# LM2596.net
KiCad netlist of a schematic drawn in Altium Designer
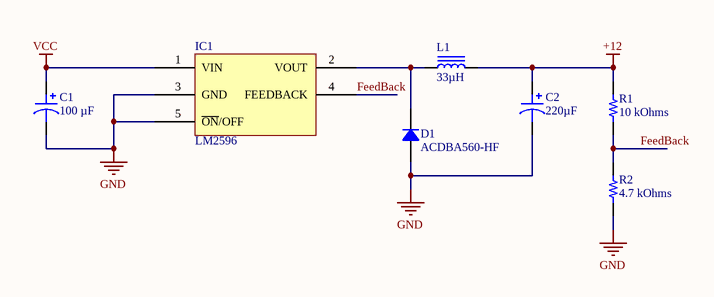
[diagram p0: LM2596.SchDoc]

(export (version "E")
  (design (tool "Eeschema 10.0.6"))
  (components
    (comp (ref "C1")
      (value "100 µF")
      (footprint "CAP AL TH D8 L3.5 H12.5")
      (description "CAP ALUM 100UF 20% 63V RADIAL")
      (fields
        (field (name "PART NUMBER") "ECA-1JM101")
        (field (name "MANUFACTURER") "Panasonic Electronic Components")
      )
      (libsource (lib "Celestial Altium Library - altium_library") (part "Polarised Capacitor"))
    )
    (comp (ref "C2")
      (value "220µF")
      (footprint "CAP TH ALUM ELEC D10.00mm S5.00mm H17.00mm")
      (description "CAP ALUM 220UF 20% 63V RADIAL")
      (fields
        (field (name "PART NUMBER") "ECA-1JM221")
        (field (name "MANUFACTURER") "Panasonic Electronic Components")
      )
      (libsource (lib "Celestial Altium Library - altium_library") (part "Polarised Capacitor"))
    )
    (comp (ref "D1")
      (value "ACDBA560-HF")
      (footprint "DO214AC SMA")
      (description "DIODE SCHOTTKY 60V 5A DO214AC")
      (libsource (lib "Celestial Altium Library - altium_library") (part "Diode"))
    )
    (comp (ref "IC1")
      (value "LM2596")
      (footprint "PcbLib1:D2PAK-LM2596")
      (libsource (lib "AltiumLib_V1") (part "LM2596"))
    )
    (comp (ref "L1")
      (value "33µH")
      (footprint "BOURNS SRR1280")
      (description "FIXED IND 33UH 3.5A 57 MOHM SMD")
      (fields (field (name "PART NUMBER") "SRR1280-330M"))
      (libsource (lib "Celestial Altium Library - altium_library") (part "Inductor"))
    )
    (comp (ref "R1")
      (value "10 kOhms")
      (footprint "RES 0805_2012")
      (description "RES 4.7K OHM 1% 1/3W 0805")
      (fields
        (field (name "PART NUMBER") "CRGP0805F4K7")
        (field (name "MANUFACTURER") "TE Connectivity Passive Product")
      )
      (libsource (lib "Celestial Altium Library - altium_library") (part "Resistor"))
    )
    (comp (ref "R2")
      (value "4.7 kOhms")
      (footprint "RES 0805_2012")
      (description "RES 4.7K OHM 1% 1/3W 0805")
      (fields
        (field (name "PART NUMBER") "CRGP0805F4K7")
        (field (name "MANUFACTURER") "TE Connectivity Passive Product")
      )
      (libsource (lib "Celestial Altium Library - altium_library") (part "Resistor"))
    )
  )
  (nets
    (net (code "1") (name "+12") (class "Default")
      (node (ref "C2") (pin "1") (pinfunction "1_1") (pintype "passive"))
      (node (ref "L1") (pin "2") (pinfunction "2_2") (pintype "passive"))
      (node (ref "R1") (pin "2") (pinfunction "2_2") (pintype "passive"))
    )
    (net (code "2") (name "/FeedBack") (class "Default")
      (node (ref "IC1") (pin "4") (pinfunction "FEEDBACK_4") (pintype "passive"))
      (node (ref "R1") (pin "1") (pinfunction "1_1") (pintype "passive"))
      (node (ref "R2") (pin "2") (pinfunction "2_2") (pintype "passive"))
    )
    (net (code "3") (name "GND") (class "Default")
      (node (ref "C1") (pin "2") (pinfunction "2_2") (pintype "passive"))
      (node (ref "C2") (pin "2") (pinfunction "2_2") (pintype "passive"))
      (node (ref "D1") (pin "1") (pinfunction "1_1") (pintype "passive"))
      (node (ref "IC1") (pin "3") (pinfunction "GND_3") (pintype "passive"))
      (node (ref "IC1") (pin "5") (pinfunction "~{ON}/OFF_5") (pintype "passive"))
      (node (ref "R2") (pin "1") (pinfunction "1_1") (pintype "passive"))
    )
    (net (code "4") (name "Net-(IC1-VOUT)") (class "Default")
      (node (ref "D1") (pin "2") (pinfunction "2_2") (pintype "passive"))
      (node (ref "IC1") (pin "2") (pinfunction "VOUT_2") (pintype "passive"))
      (node (ref "L1") (pin "1") (pinfunction "1_1") (pintype "passive"))
    )
    (net (code "5") (name "VCC") (class "Default")
      (node (ref "C1") (pin "1") (pinfunction "1_1") (pintype "passive"))
      (node (ref "IC1") (pin "1") (pinfunction "VIN_1") (pintype "passive"))
    )
  )
)
